# Bidirectional_Amp_test.net
KiCad netlist of a schematic drawn in EAGLE
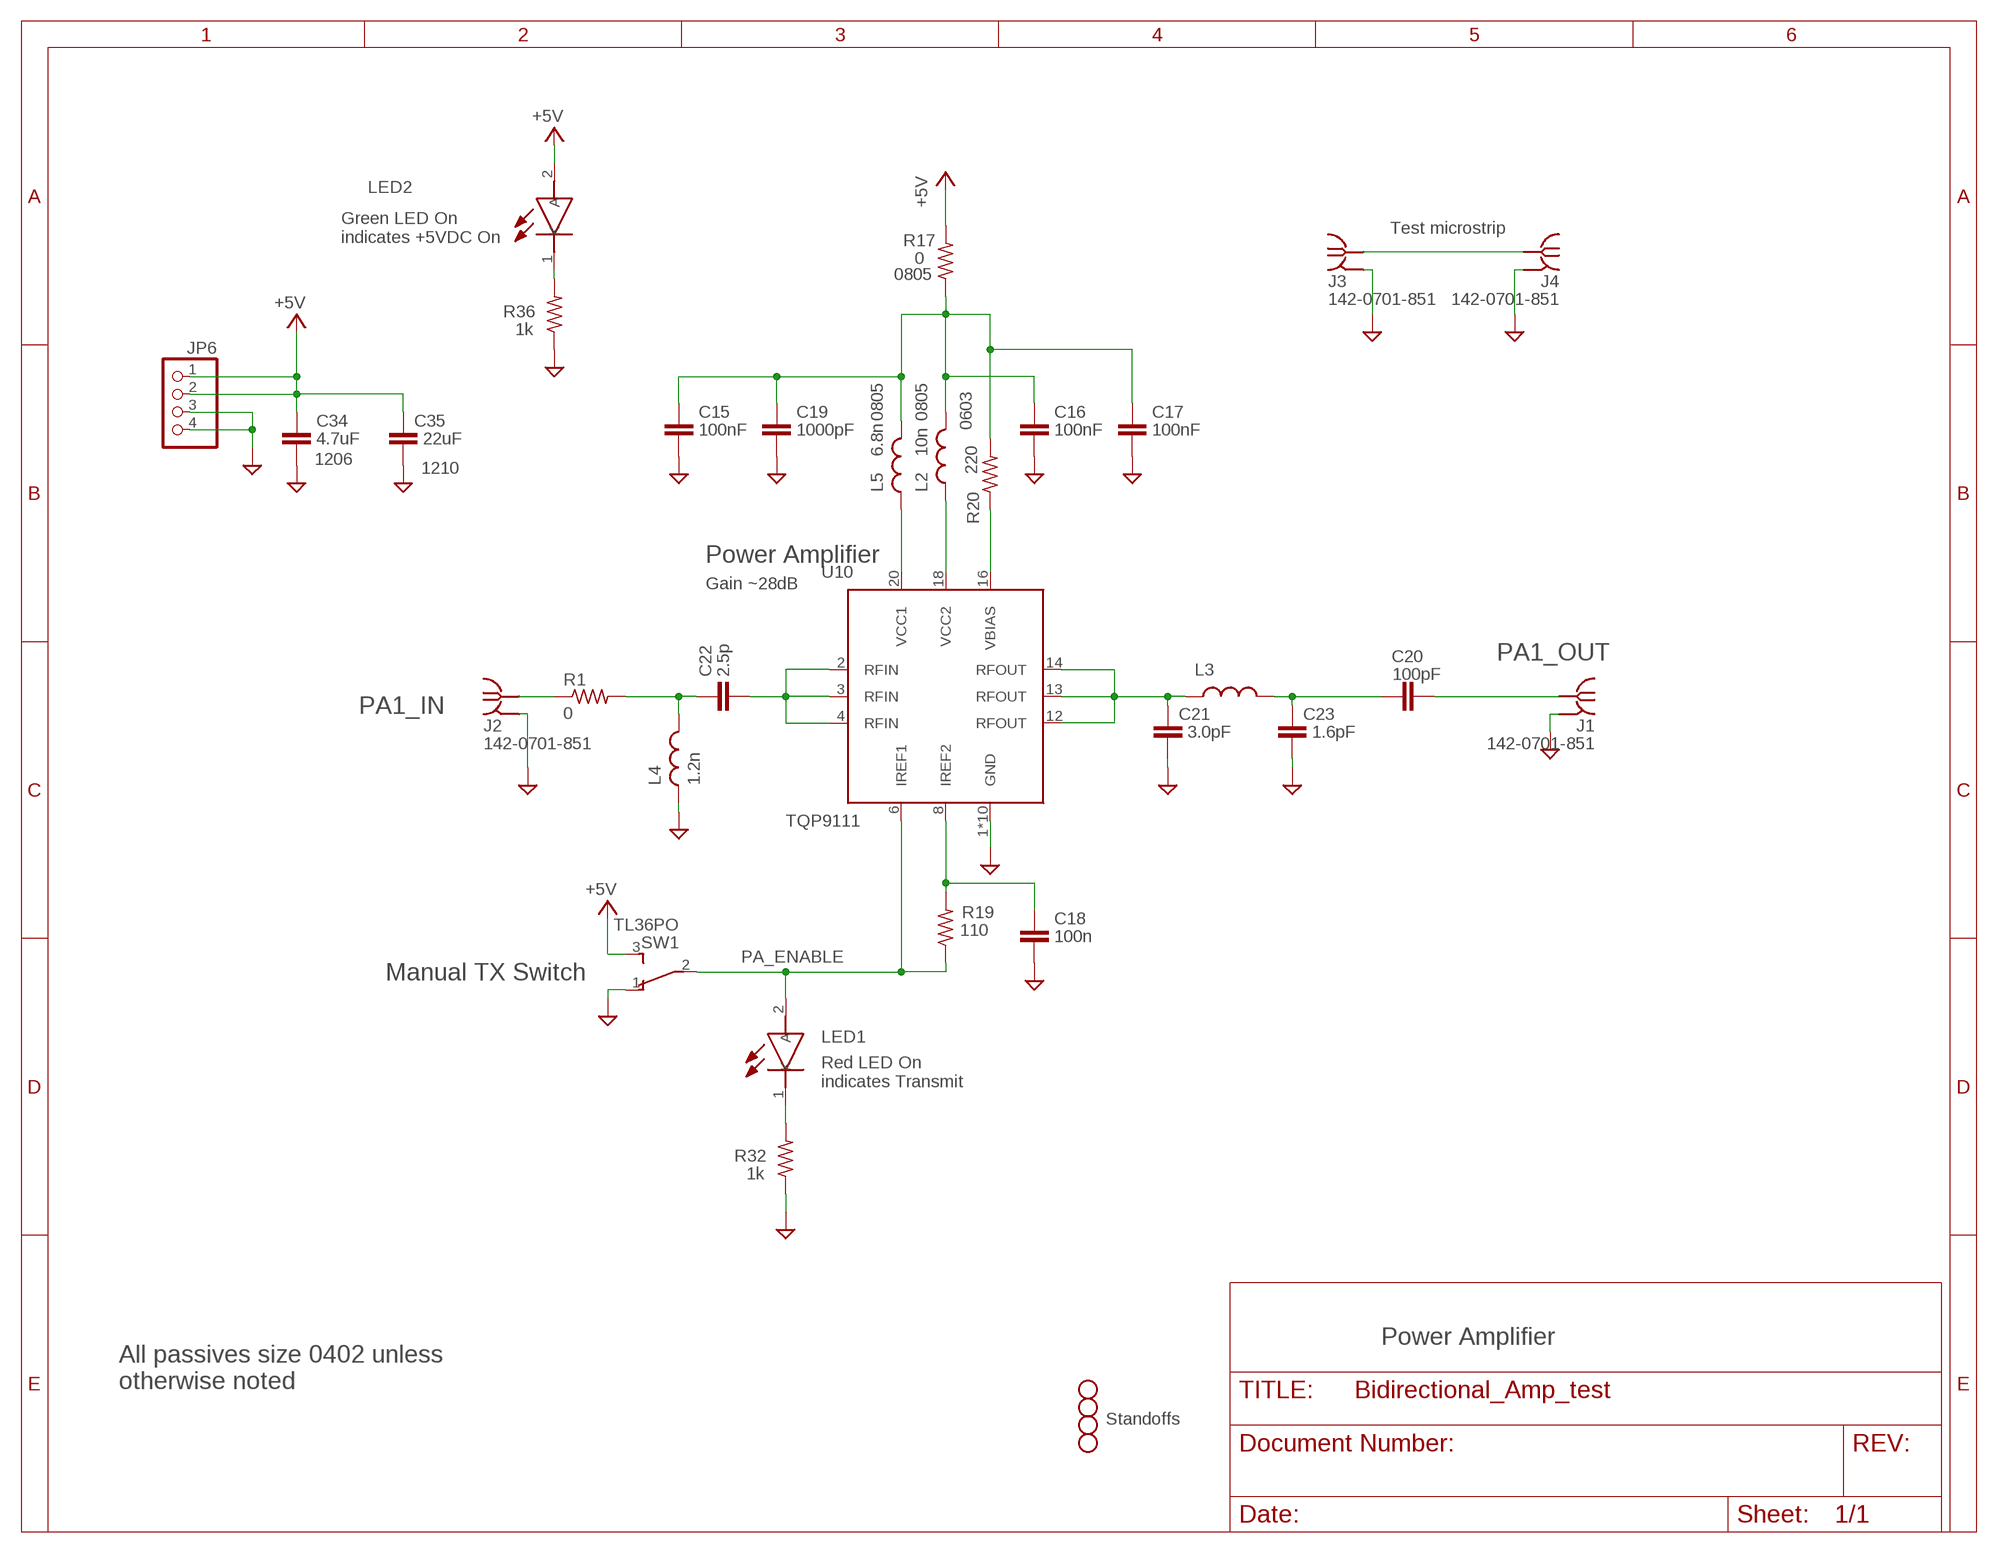
[diagram p0: schematic, sheet 1]

(export (version "E")
  (design (tool "Eeschema 10.0.6"))
  (components
    (comp (ref "C15")
      (value "100nF")
      (footprint "eagle-import:.0402-B-NOSILK")
      (description "CAP CER 0.1UF 16V X7R 0402")
      (fields (field (name "MFR") "TDK") (field (name "MPN") "CGA2B1X7R1C104K050BC"))
      (libsource (lib "eagle-import") (part "C-EU0402-B-NOSILK"))
    )
    (comp (ref "C16")
      (value "100nF")
      (footprint "eagle-import:.0402-B-NOSILK")
      (description "CAP CER 0.1UF 16V X7R 0402")
      (fields (field (name "MFR") "TDK") (field (name "MPN") "CGA2B1X7R1C104K050BC"))
      (libsource (lib "eagle-import") (part "C-EU0402-B-NOSILK"))
    )
    (comp (ref "C17")
      (value "100nF")
      (footprint "eagle-import:.0402-B-NOSILK")
      (description "CAP CER 0.1UF 16V X7R 0402")
      (fields (field (name "MFR") "TDK") (field (name "MPN") "CGA2B1X7R1C104K050BC"))
      (libsource (lib "eagle-import") (part "C-EU0402-B-NOSILK"))
    )
    (comp (ref "C18")
      (value "100n")
      (footprint "eagle-import:.0402-C-NOSILK")
      (description "CAP CER 0.1UF 16V X7R 0402")
      (fields (field (name "MFR") "TDK") (field (name "MPN") "CGA2B1X7R1C104K050BC"))
      (libsource (lib "eagle-import") (part "C-EU0402-C-NOSILK"))
    )
    (comp (ref "C19")
      (value "1000pF")
      (footprint "eagle-import:.0402-B-NOSILK")
      (description "CAP CER 1000PF 50V NP0 0402")
      (fields (field (name "MFR") "TDK") (field (name "MPN") "CGA2B2NP01H102J050BA"))
      (libsource (lib "eagle-import") (part "C-EU0402-B-NOSILK"))
    )
    (comp (ref "C20")
      (value "100pF")
      (footprint "eagle-import:.0402-C-NOSILK")
      (description "CAP CER 100PF 50V C0G/NP0 0603")
      (fields (field (name "MFR") "Murata") (field (name "MPN") "GCM1885C1H101JA16D "))
      (libsource (lib "eagle-import") (part "C-EU0402-C-NOSILK"))
    )
    (comp (ref "C21")
      (value "3.0pF")
      (footprint "eagle-import:.0402-C-NOSILK")
      (description "CAP CER 3PF 50V NP0 0402")
      (fields (field (name "MFR") "AVX") (field (name "MPN") "04025U3R0BAT2A"))
      (libsource (lib "eagle-import") (part "C-EU0402-C-NOSILK"))
    )
    (comp (ref "C22")
      (value "2.5p")
      (footprint "eagle-import:.0402-C-NOSILK")
      (description "Capacitor Thin Film 50V 2.5pF .03pFTol  0402")
      (fields (field (name "MFR") "AVX") (field (name "MPN") "04025J2R5QBSTR "))
      (libsource (lib "eagle-import") (part "C-EU0402-C-NOSILK"))
    )
    (comp (ref "C23")
      (value "1.6pF")
      (footprint "eagle-import:.0402-C-NOSILK")
      (description "CAP CER 1.6PF 50V NP0 0402")
      (fields (field (name "MFR") "AVX") (field (name "MPN") "04025U1R6BAT2A"))
      (libsource (lib "eagle-import") (part "C-EU0402-C-NOSILK"))
    )
    (comp (ref "C34")
      (value "4.7uF")
      (footprint "eagle-import:C1206")
      (description "CAP CER 4.7UF 16V X7R 1206")
      (fields (field (name "MFR") "Murata") (field (name "MPN") "GCJ31CR71C475KA01L"))
      (libsource (lib "eagle-import") (part "rcl_334_C-EUC1206"))
    )
    (comp (ref "C35")
      (value "22uF")
      (footprint "eagle-import:C1210")
      (description "CAP CER 22UF 16V X7R 1210")
      (fields (field (name "MFR") "Murata") (field (name "MPN") "GCJ32ER71C226KE01L"))
      (libsource (lib "eagle-import") (part "rcl_334_C-EUC1210"))
    )
    (comp (ref "H1")
      (value "STAND-OFFTIGHT")
      (footprint "eagle-import:STAND-OFF-TIGHT")
      (libsource (lib "eagle-import") (part "STAND-OFFTIGHT"))
    )
    (comp (ref "H2")
      (value "STAND-OFFTIGHT")
      (footprint "eagle-import:STAND-OFF-TIGHT")
      (libsource (lib "eagle-import") (part "STAND-OFFTIGHT"))
    )
    (comp (ref "H3")
      (value "STAND-OFFTIGHT")
      (footprint "eagle-import:STAND-OFF-TIGHT")
      (libsource (lib "eagle-import") (part "STAND-OFFTIGHT"))
    )
    (comp (ref "H4")
      (value "STAND-OFFTIGHT")
      (footprint "eagle-import:STAND-OFF-TIGHT")
      (libsource (lib "eagle-import") (part "STAND-OFFTIGHT"))
    )
    (comp (ref "J1")
      (value "142-0701-851")
      (footprint "eagle-import:142-0701-851")
      (description "CONN SMA JACK STR 50OHM EDGE MNT")
      (fields (field (name "MFR") "Cinch Connectivity Solutions Johnson"))
      (libsource (lib "eagle-import") (part "142-0701-851"))
    )
    (comp (ref "J2")
      (value "142-0701-851")
      (footprint "eagle-import:142-0701-851")
      (description "CONN SMA JACK STR 50OHM EDGE MNT")
      (fields (field (name "MFR") "Cinch Connectivity Solutions Johnson"))
      (libsource (lib "eagle-import") (part "142-0701-851"))
    )
    (comp (ref "J3")
      (value "142-0701-851")
      (footprint "eagle-import:142-0701-851")
      (description "CONN SMA JACK STR 50OHM EDGE MNT")
      (fields (field (name "MFR") "Cinch Connectivity Solutions Johnson"))
      (libsource (lib "eagle-import") (part "142-0701-851"))
    )
    (comp (ref "J4")
      (value "142-0701-851")
      (footprint "eagle-import:142-0701-851")
      (description "CONN SMA JACK STR 50OHM EDGE MNT")
      (fields (field (name "MFR") "Cinch Connectivity Solutions Johnson"))
      (libsource (lib "eagle-import") (part "142-0701-851"))
    )
    (comp (ref "JP6")
      (value "PINHD-1X4")
      (footprint "eagle-import:1X04")
      (description "CONN HEADER VERT 4POS 2.54MM")
      (fields (field (name "MFR") "Molex") (field (name "MPN") "0022232041"))
      (libsource (lib "eagle-import") (part "PINHD-1X4"))
    )
    (comp (ref "L2")
      (value "10n")
      (footprint "eagle-import:.0805-C-NOSILK")
      (description "Fixed Inductors 080xSQ AirCore RF 10.2 nH 2 % 2.7 A")
      (fields (field (name "MFR") "Coilcraft") (field (name "MPN") "0807SQ-10NGLB"))
      (libsource (lib "eagle-import") (part "L-US0805-C-NOSILK"))
    )
    (comp (ref "L3")
      (value "1.0nH")
      (footprint "eagle-import:.0402-C-NOSILK")
      (description "FIXED IND 1NH 500MA 100 MOHM SMD")
      (fields (field (name "MFR") "TDK Corporation") (field (name "MPN") "MLK1005S1N0ST000"))
      (libsource (lib "eagle-import") (part "L-US0402-C-NOSILK"))
    )
    (comp (ref "L4")
      (value "1.2n")
      (footprint "eagle-import:.0402-C-NOSILK")
      (description "1.2nH RF Inductor, ceramic core, 5% tol, SMT, RoHS, halogen-free")
      (fields (field (name "MFR") "Coilcraft") (field (name "MPN") "0402CT-1N2XJRW"))
      (libsource (lib "eagle-import") (part "L-US0402-C-NOSILK"))
    )
    (comp (ref "L5")
      (value "6.8n")
      (footprint "eagle-import:.0805-C-NOSILK")
      (description "Fixed Inductors 0805CS 6.8 nH 5 % 0.6 A")
      (fields (field (name "MFR") "Coilcraft") (field (name "MPN") "0805CS-060XJLC"))
      (libsource (lib "eagle-import") (part "L-US0805-C-NOSILK"))
    )
    (comp (ref "LED1")
      (value "LTST-C193KRKT-5A")
      (footprint "eagle-import:LEDC1607X80N")
      (fields (field (name "MFR") "Lite-On"))
      (libsource (lib "eagle-import") (part "LTST-C193KRKT-5A"))
    )
    (comp (ref "LED2")
      (value "LTST-C193KGKT-5A")
      (footprint "eagle-import:LEDC1607X80N")
      (fields (field (name "MFR") "Lite-On"))
      (libsource (lib "eagle-import") (part "LTST-C193KGKT-5A"))
    )
    (comp (ref "R1")
      (value "0")
      (footprint "eagle-import:.0402-C-NOSILK")
      (description "RES SMD 0 OHM JUMPER 1/10W 0402")
      (fields (field (name "MFR") "Panasonic Electronic Components") (field (name "MPN") "ERJ-2GE0R00X"))
      (libsource (lib "eagle-import") (part "R-US_0402-C-NOSILK"))
    )
    (comp (ref "R17")
      (value "0")
      (footprint "eagle-import:R0805")
      (description "RES SMD 0 OHM JUMPER 1/8W 0805")
      (fields (field (name "MFR") "Panasonic") (field (name "MPN") "ERJ-6GEY0R00V"))
      (libsource (lib "eagle-import") (part "rcl_334_R-US_R0805"))
    )
    (comp (ref "R19")
      (value "110")
      (footprint "eagle-import:.0402-B-NOSILK")
      (description "RES SMD 110 OHM 1% 1/10W 0402")
      (fields (field (name "MFR") "Panasonic") (field (name "MPN") "ERJ-2RKF1100X"))
      (libsource (lib "eagle-import") (part "R-US_0402-B-NOSILK"))
    )
    (comp (ref "R20")
      (value "220")
      (footprint "eagle-import:.0603-C-NOSILK")
      (description "RES SMD 220 OHM 1% 1/10W 0603")
      (fields (field (name "MFR") "Panasonic") (field (name "MPN") "ERJ-3EKF2200V"))
      (libsource (lib "eagle-import") (part "R-US_0603-C-NOSILK"))
    )
    (comp (ref "R32")
      (value "1k")
      (footprint "eagle-import:.0402-B-NOSILK")
      (description "RES SMD 1K OHM 5% 1/10W 0402")
      (fields (field (name "MFR") "Panasonic") (field (name "MPN") "ERJ-2GEJ102X"))
      (libsource (lib "eagle-import") (part "R-US_0402-B-NOSILK"))
    )
    (comp (ref "R36")
      (value "1k")
      (footprint "eagle-import:.0402-B-NOSILK")
      (description "RES SMD 1K OHM 5% 1/10W 0402")
      (fields (field (name "MFR") "Panasonic") (field (name "MPN") "ERJ-2GEJ102X"))
      (libsource (lib "eagle-import") (part "R-US_0402-B-NOSILK"))
    )
    (comp (ref "SW1")
      (value "TL36PO")
      (footprint "eagle-import:TL3XPO")
      (description "SWITCH TOGGLE SPDT 0.4VA 20V")
      (fields (field (name "MFR") "APEM Inc.") (field (name "MPN") "TL36P005000"))
      (libsource (lib "eagle-import") (part "TL36PO"))
    )
    (comp (ref "U10")
      (value "TQP9111")
      (footprint "eagle-import:QFN50P400X400X102-21N")
      (fields (field (name "MFR") "Qorvo"))
      (libsource (lib "eagle-import") (part "TQP9111"))
    )
  )
  (nets
    (net (code "1") (name "+5V") (class "Default")
      (node (ref "C34") (pin "1") (pinfunction "1_1") (pintype "passive"))
      (node (ref "C35") (pin "1") (pinfunction "1_1") (pintype "passive"))
      (node (ref "JP6") (pin "1") (pinfunction "1_1") (pintype "passive"))
      (node (ref "JP6") (pin "2") (pinfunction "2_2") (pintype "passive"))
      (node (ref "LED2") (pin "2") (pinfunction "A_2") (pintype "bidirectional"))
      (node (ref "R17") (pin "2") (pinfunction "2_2") (pintype "passive"))
      (node (ref "SW1") (pin "3") (pinfunction "S_3") (pintype "passive"))
    )
    (net (code "2") (name "/PA1_OUT") (class "Default")
      (node (ref "C20") (pin "2") (pinfunction "2_2") (pintype "passive"))
      (node (ref "J1") (pin "RF1") (pinfunction "RF_RF1") (pintype "bidirectional"))
    )
    (net (code "3") (name "/PA_ENABLE") (class "Default")
      (node (ref "LED1") (pin "2") (pinfunction "A_2") (pintype "bidirectional"))
      (node (ref "R19") (pin "1") (pinfunction "1_1") (pintype "passive"))
      (node (ref "SW1") (pin "2") (pinfunction "P_2") (pintype "passive"))
      (node (ref "U10") (pin "6") (pinfunction "IREF1_6") (pintype "passive"))
    )
    (net (code "4") (name "GND") (class "Default")
      (node (ref "C15") (pin "2") (pinfunction "2_2") (pintype "passive"))
      (node (ref "C16") (pin "2") (pinfunction "2_2") (pintype "passive"))
      (node (ref "C17") (pin "2") (pinfunction "2_2") (pintype "passive"))
      (node (ref "C18") (pin "2") (pinfunction "2_2") (pintype "passive"))
      (node (ref "C19") (pin "2") (pinfunction "2_2") (pintype "passive"))
      (node (ref "C21") (pin "2") (pinfunction "2_2") (pintype "passive"))
      (node (ref "C23") (pin "2") (pinfunction "2_2") (pintype "passive"))
      (node (ref "C34") (pin "2") (pinfunction "2_2") (pintype "passive"))
      (node (ref "C35") (pin "2") (pinfunction "2_2") (pintype "passive"))
      (node (ref "J1") (pin "GND1") (pinfunction "GND_GND1") (pintype "bidirectional"))
      (node (ref "J1") (pin "GND2") (pinfunction "GND_GND2") (pintype "bidirectional"))
      (node (ref "J1") (pin "GND3") (pinfunction "GND_GND3") (pintype "bidirectional"))
      (node (ref "J1") (pin "GND4") (pinfunction "GND_GND4") (pintype "bidirectional"))
      (node (ref "J2") (pin "GND1") (pinfunction "GND_GND1") (pintype "bidirectional"))
      (node (ref "J2") (pin "GND2") (pinfunction "GND_GND2") (pintype "bidirectional"))
      (node (ref "J2") (pin "GND3") (pinfunction "GND_GND3") (pintype "bidirectional"))
      (node (ref "J2") (pin "GND4") (pinfunction "GND_GND4") (pintype "bidirectional"))
      (node (ref "J3") (pin "GND1") (pinfunction "GND_GND1") (pintype "bidirectional"))
      (node (ref "J3") (pin "GND2") (pinfunction "GND_GND2") (pintype "bidirectional"))
      (node (ref "J3") (pin "GND3") (pinfunction "GND_GND3") (pintype "bidirectional"))
      (node (ref "J3") (pin "GND4") (pinfunction "GND_GND4") (pintype "bidirectional"))
      (node (ref "J4") (pin "GND1") (pinfunction "GND_GND1") (pintype "bidirectional"))
      (node (ref "J4") (pin "GND2") (pinfunction "GND_GND2") (pintype "bidirectional"))
      (node (ref "J4") (pin "GND3") (pinfunction "GND_GND3") (pintype "bidirectional"))
      (node (ref "J4") (pin "GND4") (pinfunction "GND_GND4") (pintype "bidirectional"))
      (node (ref "JP6") (pin "3") (pinfunction "3_3") (pintype "passive"))
      (node (ref "JP6") (pin "4") (pinfunction "4_4") (pintype "passive"))
      (node (ref "L4") (pin "1") (pinfunction "1_1") (pintype "passive"))
      (node (ref "R32") (pin "1") (pinfunction "1_1") (pintype "passive"))
      (node (ref "R36") (pin "1") (pinfunction "1_1") (pintype "passive"))
      (node (ref "SW1") (pin "1") (pinfunction "O_1") (pintype "passive"))
      (node (ref "U10") (pin "1") (pinfunction "GND_1") (pintype "power_in"))
      (node (ref "U10") (pin "10") (pinfunction "GND_10") (pintype "power_in"))
      (node (ref "U10") (pin "11") (pinfunction "GND_11") (pintype "power_in"))
      (node (ref "U10") (pin "15") (pinfunction "GND_15") (pintype "power_in"))
      (node (ref "U10") (pin "17") (pinfunction "GND_17") (pintype "power_in"))
      (node (ref "U10") (pin "19") (pinfunction "GND_19") (pintype "power_in"))
      (node (ref "U10") (pin "21") (pinfunction "GND_21") (pintype "power_in"))
      (node (ref "U10") (pin "5") (pinfunction "GND_5") (pintype "power_in"))
      (node (ref "U10") (pin "7") (pinfunction "GND_7") (pintype "power_in"))
      (node (ref "U10") (pin "9") (pinfunction "GND_9") (pintype "power_in"))
    )
    (net (code "5") (name "Net-(C15-Pad1)") (class "Default")
      (node (ref "C15") (pin "1") (pinfunction "1_1") (pintype "passive"))
      (node (ref "C16") (pin "1") (pinfunction "1_1") (pintype "passive"))
      (node (ref "C17") (pin "1") (pinfunction "1_1") (pintype "passive"))
      (node (ref "C19") (pin "1") (pinfunction "1_1") (pintype "passive"))
      (node (ref "L2") (pin "2") (pinfunction "2_2") (pintype "passive"))
      (node (ref "L5") (pin "2") (pinfunction "2_2") (pintype "passive"))
      (node (ref "R17") (pin "1") (pinfunction "1_1") (pintype "passive"))
      (node (ref "R20") (pin "2") (pinfunction "2_2") (pintype "passive"))
    )
    (net (code "6") (name "Net-(C20-Pad1)") (class "Default")
      (node (ref "C20") (pin "1") (pinfunction "1_1") (pintype "passive"))
      (node (ref "C23") (pin "1") (pinfunction "1_1") (pintype "passive"))
      (node (ref "L3") (pin "2") (pinfunction "2_2") (pintype "passive"))
    )
    (net (code "7") (name "Net-(C21-Pad1)") (class "Default")
      (node (ref "C21") (pin "1") (pinfunction "1_1") (pintype "passive"))
      (node (ref "L3") (pin "1") (pinfunction "1_1") (pintype "passive"))
      (node (ref "U10") (pin "12") (pinfunction "RFOUT_12") (pintype "output"))
      (node (ref "U10") (pin "13") (pinfunction "RFOUT_13") (pintype "output"))
      (node (ref "U10") (pin "14") (pinfunction "RFOUT_14") (pintype "output"))
    )
    (net (code "8") (name "Net-(C22-Pad1)") (class "Default")
      (node (ref "C22") (pin "1") (pinfunction "1_1") (pintype "passive"))
      (node (ref "L4") (pin "2") (pinfunction "2_2") (pintype "passive"))
      (node (ref "R1") (pin "2") (pinfunction "2_2") (pintype "passive"))
    )
    (net (code "9") (name "Net-(C22-Pad2)") (class "Default")
      (node (ref "C22") (pin "2") (pinfunction "2_2") (pintype "passive"))
      (node (ref "U10") (pin "2") (pinfunction "RFIN_2") (pintype "input"))
      (node (ref "U10") (pin "3") (pinfunction "RFIN_3") (pintype "input"))
      (node (ref "U10") (pin "4") (pinfunction "RFIN_4") (pintype "input"))
    )
    (net (code "10") (name "Net-(J2-RF)") (class "Default")
      (node (ref "J2") (pin "RF1") (pinfunction "RF_RF1") (pintype "bidirectional"))
      (node (ref "R1") (pin "1") (pinfunction "1_1") (pintype "passive"))
    )
    (net (code "11") (name "Net-(J3-RF)") (class "Default")
      (node (ref "J3") (pin "RF1") (pinfunction "RF_RF1") (pintype "bidirectional"))
      (node (ref "J4") (pin "RF1") (pinfunction "RF_RF1") (pintype "bidirectional"))
    )
    (net (code "12") (name "Net-(LED1-K)") (class "Default")
      (node (ref "LED1") (pin "1") (pinfunction "K_1") (pintype "bidirectional"))
      (node (ref "R32") (pin "2") (pinfunction "2_2") (pintype "passive"))
    )
    (net (code "13") (name "Net-(LED2-K)") (class "Default")
      (node (ref "LED2") (pin "1") (pinfunction "K_1") (pintype "bidirectional"))
      (node (ref "R36") (pin "2") (pinfunction "2_2") (pintype "passive"))
    )
    (net (code "14") (name "Net-(U10-IREF2)") (class "Default")
      (node (ref "C18") (pin "1") (pinfunction "1_1") (pintype "passive"))
      (node (ref "R19") (pin "2") (pinfunction "2_2") (pintype "passive"))
      (node (ref "U10") (pin "8") (pinfunction "IREF2_8") (pintype "passive"))
    )
    (net (code "15") (name "Net-(U10-VBIAS)") (class "Default")
      (node (ref "R20") (pin "1") (pinfunction "1_1") (pintype "passive"))
      (node (ref "U10") (pin "16") (pinfunction "VBIAS_16") (pintype "power_in"))
    )
    (net (code "16") (name "Net-(U10-VCC1)") (class "Default")
      (node (ref "L5") (pin "1") (pinfunction "1_1") (pintype "passive"))
      (node (ref "U10") (pin "20") (pinfunction "VCC1_20") (pintype "power_in"))
    )
    (net (code "17") (name "Net-(U10-VCC2)") (class "Default")
      (node (ref "L2") (pin "1") (pinfunction "1_1") (pintype "passive"))
      (node (ref "U10") (pin "18") (pinfunction "VCC2_18") (pintype "power_in"))
    )
  )
)
